# ble_terrain_twister.net
KiCad netlist of a schematic drawn in EAGLE
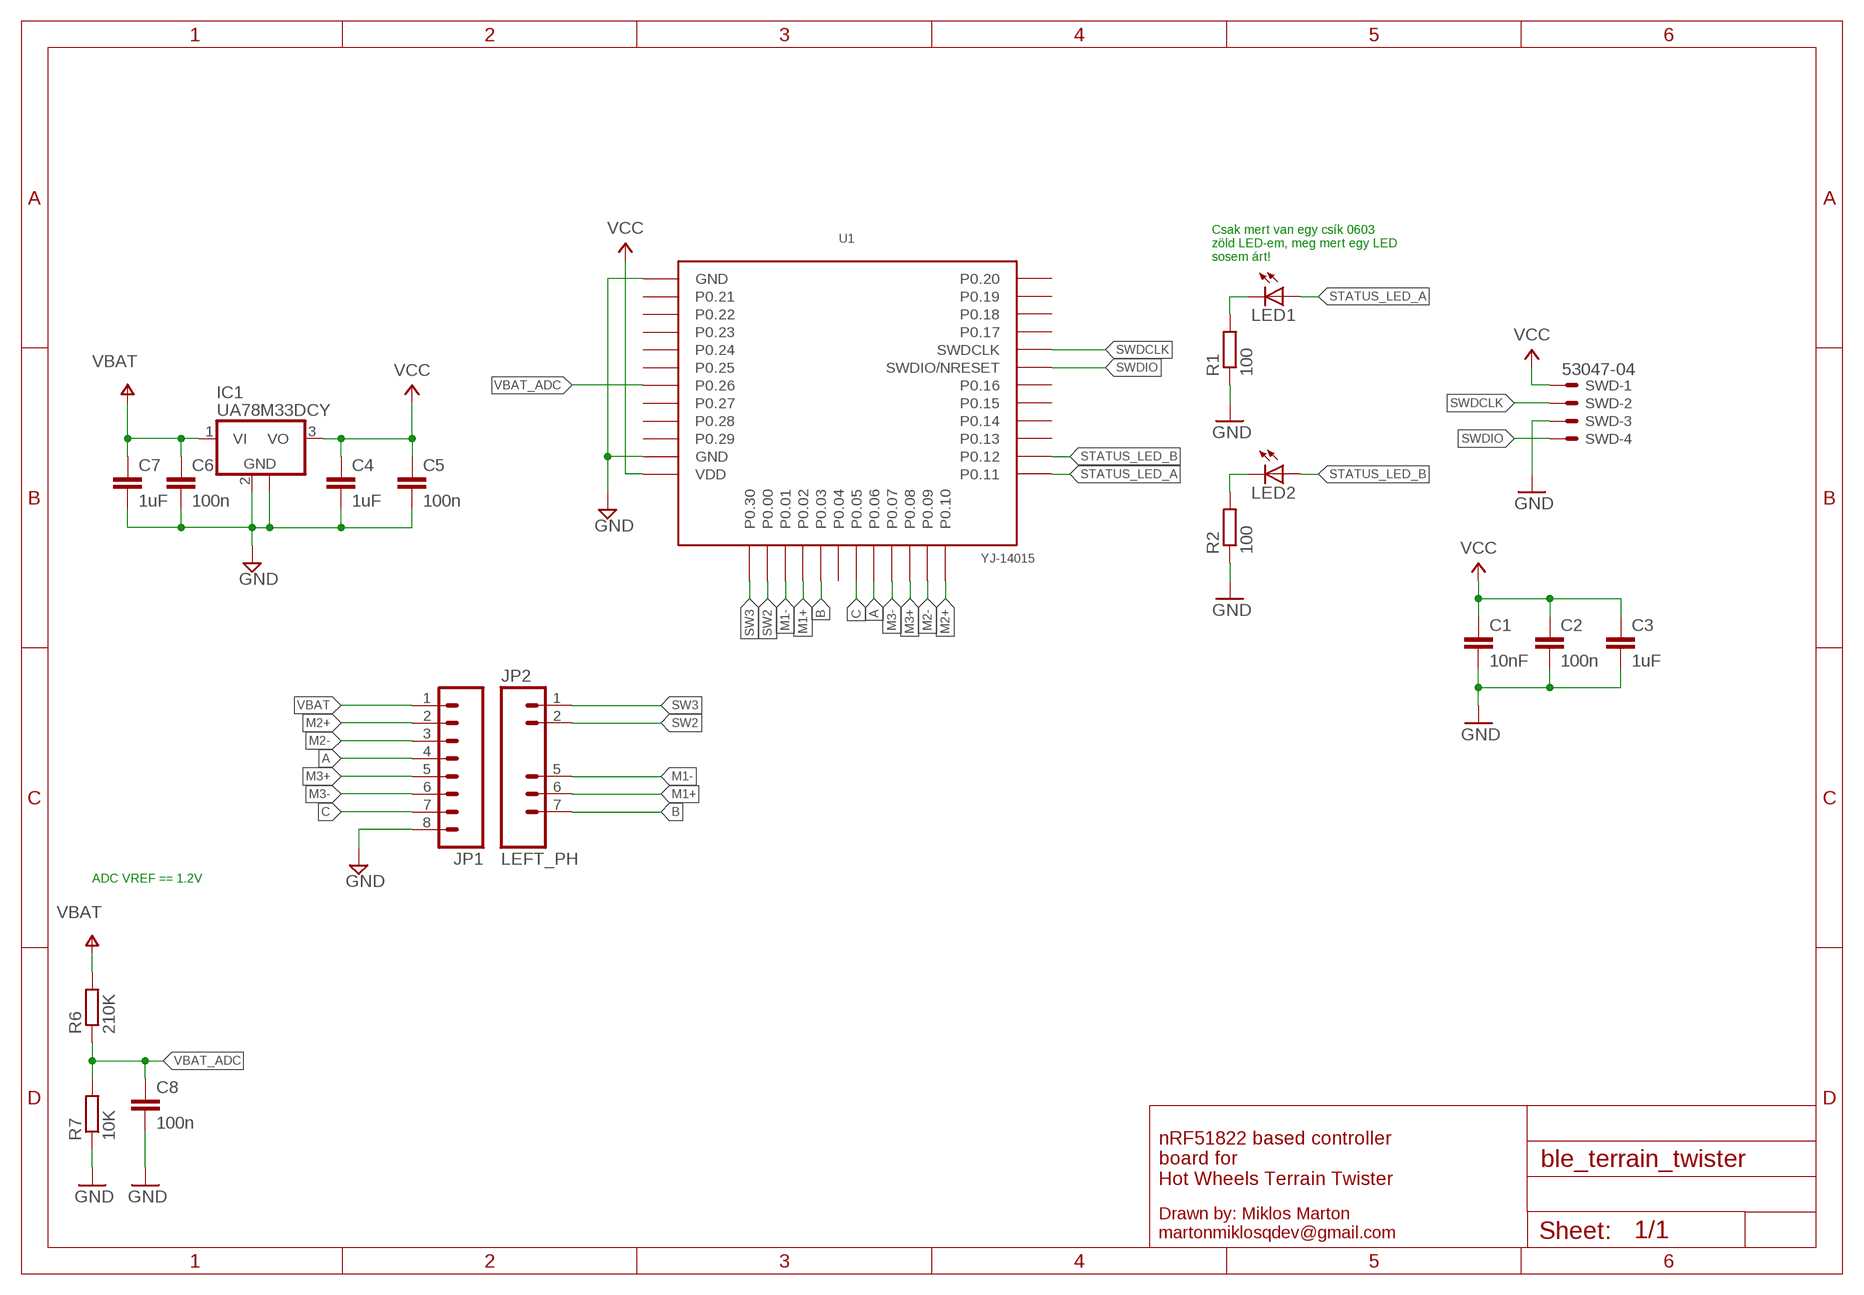
[diagram p0: schematic, sheet 1]

(export (version "E")
  (design (tool "Eeschema 10.0.6"))
  (components
    (comp (ref "C1")
      (value "10nF")
      (footprint "eagle-import:C0603")
      (libsource (lib "eagle-import") (part "C-EUC0603"))
    )
    (comp (ref "C2")
      (value "100n")
      (footprint "eagle-import:C0603")
      (libsource (lib "eagle-import") (part "C-EUC0603"))
    )
    (comp (ref "C3")
      (value "1uF")
      (footprint "eagle-import:C0603")
      (libsource (lib "eagle-import") (part "C-EUC0603"))
    )
    (comp (ref "C4")
      (value "1uF")
      (footprint "eagle-import:C0603")
      (libsource (lib "eagle-import") (part "C-EUC0603"))
    )
    (comp (ref "C5")
      (value "100n")
      (footprint "eagle-import:C0603")
      (libsource (lib "eagle-import") (part "C-EUC0603"))
    )
    (comp (ref "C6")
      (value "100n")
      (footprint "eagle-import:C0603")
      (libsource (lib "eagle-import") (part "C-EUC0603"))
    )
    (comp (ref "C7")
      (value "1uF")
      (footprint "eagle-import:C0603")
      (libsource (lib "eagle-import") (part "C-EUC0603"))
    )
    (comp (ref "C8")
      (value "100n")
      (footprint "eagle-import:C0603")
      (libsource (lib "eagle-import") (part "C-EUC0603"))
    )
    (comp (ref "IC1")
      (value "UA78M33DCY")
      (footprint "eagle-import:SOT223")
      (libsource (lib "eagle-import") (part "UA78MDCY33"))
    )
    (comp (ref "JP1")
      (value "M081.27MM")
      (footprint "eagle-import:1X08_1.27MM")
      (libsource (lib "eagle-import") (part "M081.27MM"))
    )
    (comp (ref "JP2")
      (value "LEFT_PH")
      (footprint "eagle-import:1X08_1.27MM")
      (libsource (lib "eagle-import") (part "LEFT_PH"))
    )
    (comp (ref "LED1")
      (value "LED0603")
      (footprint "eagle-import:CHIPLED_0603")
      (libsource (lib "eagle-import") (part "LED0603"))
    )
    (comp (ref "LED2")
      (value "LED0603")
      (footprint "eagle-import:CHIPLED_0603")
      (libsource (lib "eagle-import") (part "LED0603"))
    )
    (comp (ref "R1")
      (value "100")
      (footprint "eagle-import:R0603")
      (libsource (lib "eagle-import") (part "R-EU_R0603"))
    )
    (comp (ref "R2")
      (value "100")
      (footprint "eagle-import:R0603")
      (libsource (lib "eagle-import") (part "R-EU_R0603"))
    )
    (comp (ref "R6")
      (value "210K")
      (footprint "eagle-import:R0603")
      (libsource (lib "eagle-import") (part "R-EU_R0603"))
    )
    (comp (ref "R7")
      (value "10K")
      (footprint "eagle-import:R0603")
      (libsource (lib "eagle-import") (part "R-EU_R0603"))
    )
    (comp (ref "SWD")
      (value "53047-04")
      (footprint "eagle-import:53047-04")
      (fields (field (name "MF") "WALDOM/MOLEX") (field (name "MPN") "53047-0410"))
      (libsource (lib "eagle-import") (part "53?-04047"))
    )
    (comp (ref "U1")
      (value "YJ-14015")
      (footprint "eagle-import:YJ-14015")
      (libsource (lib "eagle-import") (part "YJ-14015"))
    )
  )
  (nets
    (net (code "1") (name "A") (class "Default")
      (node (ref "JP1") (pin "4") (pinfunction "4_4") (pintype "passive"))
      (node (ref "U1") (pin "P.06") (pinfunction "P0.06_P.06") (pintype "bidirectional"))
    )
    (net (code "2") (name "B") (class "Default")
      (node (ref "JP2") (pin "7") (pinfunction "7_7") (pintype "passive"))
      (node (ref "U1") (pin "P.03") (pinfunction "P0.03_P.03") (pintype "bidirectional"))
    )
    (net (code "3") (name "C") (class "Default")
      (node (ref "JP1") (pin "7") (pinfunction "7_7") (pintype "passive"))
      (node (ref "U1") (pin "P.05") (pinfunction "P0.05_P.05") (pintype "bidirectional"))
    )
    (net (code "4") (name "GND") (class "Default")
      (node (ref "C1") (pin "2") (pinfunction "2_2") (pintype "passive"))
      (node (ref "C2") (pin "2") (pinfunction "2_2") (pintype "passive"))
      (node (ref "C3") (pin "2") (pinfunction "2_2") (pintype "passive"))
      (node (ref "C4") (pin "2") (pinfunction "2_2") (pintype "passive"))
      (node (ref "C5") (pin "2") (pinfunction "2_2") (pintype "passive"))
      (node (ref "C6") (pin "2") (pinfunction "2_2") (pintype "passive"))
      (node (ref "C7") (pin "2") (pinfunction "2_2") (pintype "passive"))
      (node (ref "C8") (pin "2") (pinfunction "2_2") (pintype "passive"))
      (node (ref "IC1") (pin "2") (pinfunction "GND_2") (pintype "passive"))
      (node (ref "IC1") (pin "4") (pinfunction "GND_4") (pintype "passive"))
      (node (ref "JP1") (pin "8") (pinfunction "8_8") (pintype "passive"))
      (node (ref "R1") (pin "1") (pinfunction "1_1") (pintype "passive"))
      (node (ref "R2") (pin "1") (pinfunction "1_1") (pintype "passive"))
      (node (ref "R7") (pin "1") (pinfunction "1_1") (pintype "passive"))
      (node (ref "SWD") (pin "3") (pinfunction "S_3") (pintype "passive"))
      (node (ref "U1") (pin "GND") (pinfunction "GND_GND") (pintype "passive"))
      (node (ref "U1") (pin "GND@2") (pinfunction "GND_GND@2") (pintype "passive"))
    )
    (net (code "5") (name "M1+") (class "Default")
      (node (ref "JP2") (pin "6") (pinfunction "6_6") (pintype "passive"))
      (node (ref "U1") (pin "P.02") (pinfunction "P0.02_P.02") (pintype "bidirectional"))
    )
    (net (code "6") (name "M1-") (class "Default")
      (node (ref "JP2") (pin "5") (pinfunction "5_5") (pintype "passive"))
      (node (ref "U1") (pin "P.01") (pinfunction "P0.01_P.01") (pintype "bidirectional"))
    )
    (net (code "7") (name "M2+") (class "Default")
      (node (ref "JP1") (pin "2") (pinfunction "2_2") (pintype "passive"))
      (node (ref "U1") (pin "P.10") (pinfunction "P0.10_P.10") (pintype "bidirectional"))
    )
    (net (code "8") (name "M2-") (class "Default")
      (node (ref "JP1") (pin "3") (pinfunction "3_3") (pintype "passive"))
      (node (ref "U1") (pin "P.09") (pinfunction "P0.09_P.09") (pintype "bidirectional"))
    )
    (net (code "9") (name "M3+") (class "Default")
      (node (ref "JP1") (pin "5") (pinfunction "5_5") (pintype "passive"))
      (node (ref "U1") (pin "P.08") (pinfunction "P0.08_P.08") (pintype "bidirectional"))
    )
    (net (code "10") (name "M3-") (class "Default")
      (node (ref "JP1") (pin "6") (pinfunction "6_6") (pintype "passive"))
      (node (ref "U1") (pin "P.07") (pinfunction "P0.07_P.07") (pintype "bidirectional"))
    )
    (net (code "11") (name "Net-(LED1-PadC)") (class "Default")
      (node (ref "LED1") (pin "C") (pinfunction "C_C") (pintype "passive"))
      (node (ref "R1") (pin "2") (pinfunction "2_2") (pintype "passive"))
    )
    (net (code "12") (name "Net-(LED2-PadC)") (class "Default")
      (node (ref "LED2") (pin "C") (pinfunction "C_C") (pintype "passive"))
      (node (ref "R2") (pin "2") (pinfunction "2_2") (pintype "passive"))
    )
    (net (code "13") (name "STATUS_LED_A") (class "Default")
      (node (ref "LED1") (pin "A") (pinfunction "A_A") (pintype "passive"))
      (node (ref "U1") (pin "P.11") (pinfunction "P0.11_P.11") (pintype "bidirectional"))
    )
    (net (code "14") (name "STATUS_LED_B") (class "Default")
      (node (ref "LED2") (pin "A") (pinfunction "A_A") (pintype "passive"))
      (node (ref "U1") (pin "P.12") (pinfunction "P0.12_P.12") (pintype "bidirectional"))
    )
    (net (code "15") (name "SW2") (class "Default")
      (node (ref "JP2") (pin "2") (pinfunction "2_2") (pintype "passive"))
      (node (ref "U1") (pin "P.00") (pinfunction "P0.00_P.00") (pintype "bidirectional"))
    )
    (net (code "16") (name "SW3") (class "Default")
      (node (ref "JP2") (pin "1") (pinfunction "1_1") (pintype "passive"))
      (node (ref "U1") (pin "P.30") (pinfunction "P0.30_P.30") (pintype "bidirectional"))
    )
    (net (code "17") (name "SWDCLK") (class "Default")
      (node (ref "SWD") (pin "2") (pinfunction "S_2") (pintype "passive"))
      (node (ref "U1") (pin "SWDCLK") (pinfunction "SWDCLK_SWDCLK") (pintype "input"))
    )
    (net (code "18") (name "SWDIO") (class "Default")
      (node (ref "SWD") (pin "4") (pinfunction "S_4") (pintype "passive"))
      (node (ref "U1") (pin "SWDIO") (pinfunction "SWDIO/NRESET_SWDIO") (pintype "bidirectional"))
    )
    (net (code "19") (name "VBAT") (class "Default")
      (node (ref "C6") (pin "1") (pinfunction "1_1") (pintype "passive"))
      (node (ref "C7") (pin "1") (pinfunction "1_1") (pintype "passive"))
      (node (ref "IC1") (pin "1") (pinfunction "VI_1") (pintype "input"))
      (node (ref "JP1") (pin "1") (pinfunction "1_1") (pintype "passive"))
      (node (ref "R6") (pin "2") (pinfunction "2_2") (pintype "passive"))
    )
    (net (code "20") (name "VBAT_ADC") (class "Default")
      (node (ref "C8") (pin "1") (pinfunction "1_1") (pintype "passive"))
      (node (ref "R6") (pin "1") (pinfunction "1_1") (pintype "passive"))
      (node (ref "R7") (pin "2") (pinfunction "2_2") (pintype "passive"))
      (node (ref "U1") (pin "P.26") (pinfunction "P0.26_P.26") (pintype "bidirectional"))
    )
    (net (code "21") (name "VCC") (class "Default")
      (node (ref "C1") (pin "1") (pinfunction "1_1") (pintype "passive"))
      (node (ref "C2") (pin "1") (pinfunction "1_1") (pintype "passive"))
      (node (ref "C3") (pin "1") (pinfunction "1_1") (pintype "passive"))
      (node (ref "C4") (pin "1") (pinfunction "1_1") (pintype "passive"))
      (node (ref "C5") (pin "1") (pinfunction "1_1") (pintype "passive"))
      (node (ref "IC1") (pin "3") (pinfunction "VO_3") (pintype "passive"))
      (node (ref "SWD") (pin "1") (pinfunction "S_1") (pintype "passive"))
      (node (ref "U1") (pin "VDD") (pinfunction "VDD_VDD") (pintype "passive"))
    )
    (net (code "22") (name "unconnected-(U1-P0.04-PadP.04)") (class "Default")
      (node (ref "U1") (pin "P.04") (pinfunction "P0.04_P.04") (pintype "bidirectional"))
    )
    (net (code "23") (name "unconnected-(U1-P0.13-PadP.13)") (class "Default")
      (node (ref "U1") (pin "P.13") (pinfunction "P0.13_P.13") (pintype "bidirectional"))
    )
    (net (code "24") (name "unconnected-(U1-P0.14-PadP.14)") (class "Default")
      (node (ref "U1") (pin "P.14") (pinfunction "P0.14_P.14") (pintype "bidirectional"))
    )
    (net (code "25") (name "unconnected-(U1-P0.15-PadP.15)") (class "Default")
      (node (ref "U1") (pin "P.15") (pinfunction "P0.15_P.15") (pintype "bidirectional"))
    )
    (net (code "26") (name "unconnected-(U1-P0.16-PadP.16)") (class "Default")
      (node (ref "U1") (pin "P.16") (pinfunction "P0.16_P.16") (pintype "bidirectional"))
    )
    (net (code "27") (name "unconnected-(U1-P0.17-PadP.17)") (class "Default")
      (node (ref "U1") (pin "P.17") (pinfunction "P0.17_P.17") (pintype "bidirectional"))
    )
    (net (code "28") (name "unconnected-(U1-P0.18-PadP.18)") (class "Default")
      (node (ref "U1") (pin "P.18") (pinfunction "P0.18_P.18") (pintype "bidirectional"))
    )
    (net (code "29") (name "unconnected-(U1-P0.19-PadP.19)") (class "Default")
      (node (ref "U1") (pin "P.19") (pinfunction "P0.19_P.19") (pintype "bidirectional"))
    )
    (net (code "30") (name "unconnected-(U1-P0.20-PadP.20)") (class "Default")
      (node (ref "U1") (pin "P.20") (pinfunction "P0.20_P.20") (pintype "bidirectional"))
    )
    (net (code "31") (name "unconnected-(U1-P0.21-PadP.21)") (class "Default")
      (node (ref "U1") (pin "P.21") (pinfunction "P0.21_P.21") (pintype "bidirectional"))
    )
    (net (code "32") (name "unconnected-(U1-P0.22-PadP.22)") (class "Default")
      (node (ref "U1") (pin "P.22") (pinfunction "P0.22_P.22") (pintype "bidirectional"))
    )
    (net (code "33") (name "unconnected-(U1-P0.23-PadP.23)") (class "Default")
      (node (ref "U1") (pin "P.23") (pinfunction "P0.23_P.23") (pintype "bidirectional"))
    )
    (net (code "34") (name "unconnected-(U1-P0.24-PadP.24)") (class "Default")
      (node (ref "U1") (pin "P.24") (pinfunction "P0.24_P.24") (pintype "bidirectional"))
    )
    (net (code "35") (name "unconnected-(U1-P0.25-PadP.25)") (class "Default")
      (node (ref "U1") (pin "P.25") (pinfunction "P0.25_P.25") (pintype "bidirectional"))
    )
    (net (code "36") (name "unconnected-(U1-P0.27-PadP.27)") (class "Default")
      (node (ref "U1") (pin "P.27") (pinfunction "P0.27_P.27") (pintype "bidirectional"))
    )
    (net (code "37") (name "unconnected-(U1-P0.28-PadP.28)") (class "Default")
      (node (ref "U1") (pin "P.28") (pinfunction "P0.28_P.28") (pintype "bidirectional"))
    )
    (net (code "38") (name "unconnected-(U1-P0.29-PadP.29)") (class "Default")
      (node (ref "U1") (pin "P.29") (pinfunction "P0.29_P.29") (pintype "bidirectional"))
    )
  )
)
